# BAAAHS-BRN01-D.net
KiCad netlist of a schematic drawn in EAGLE
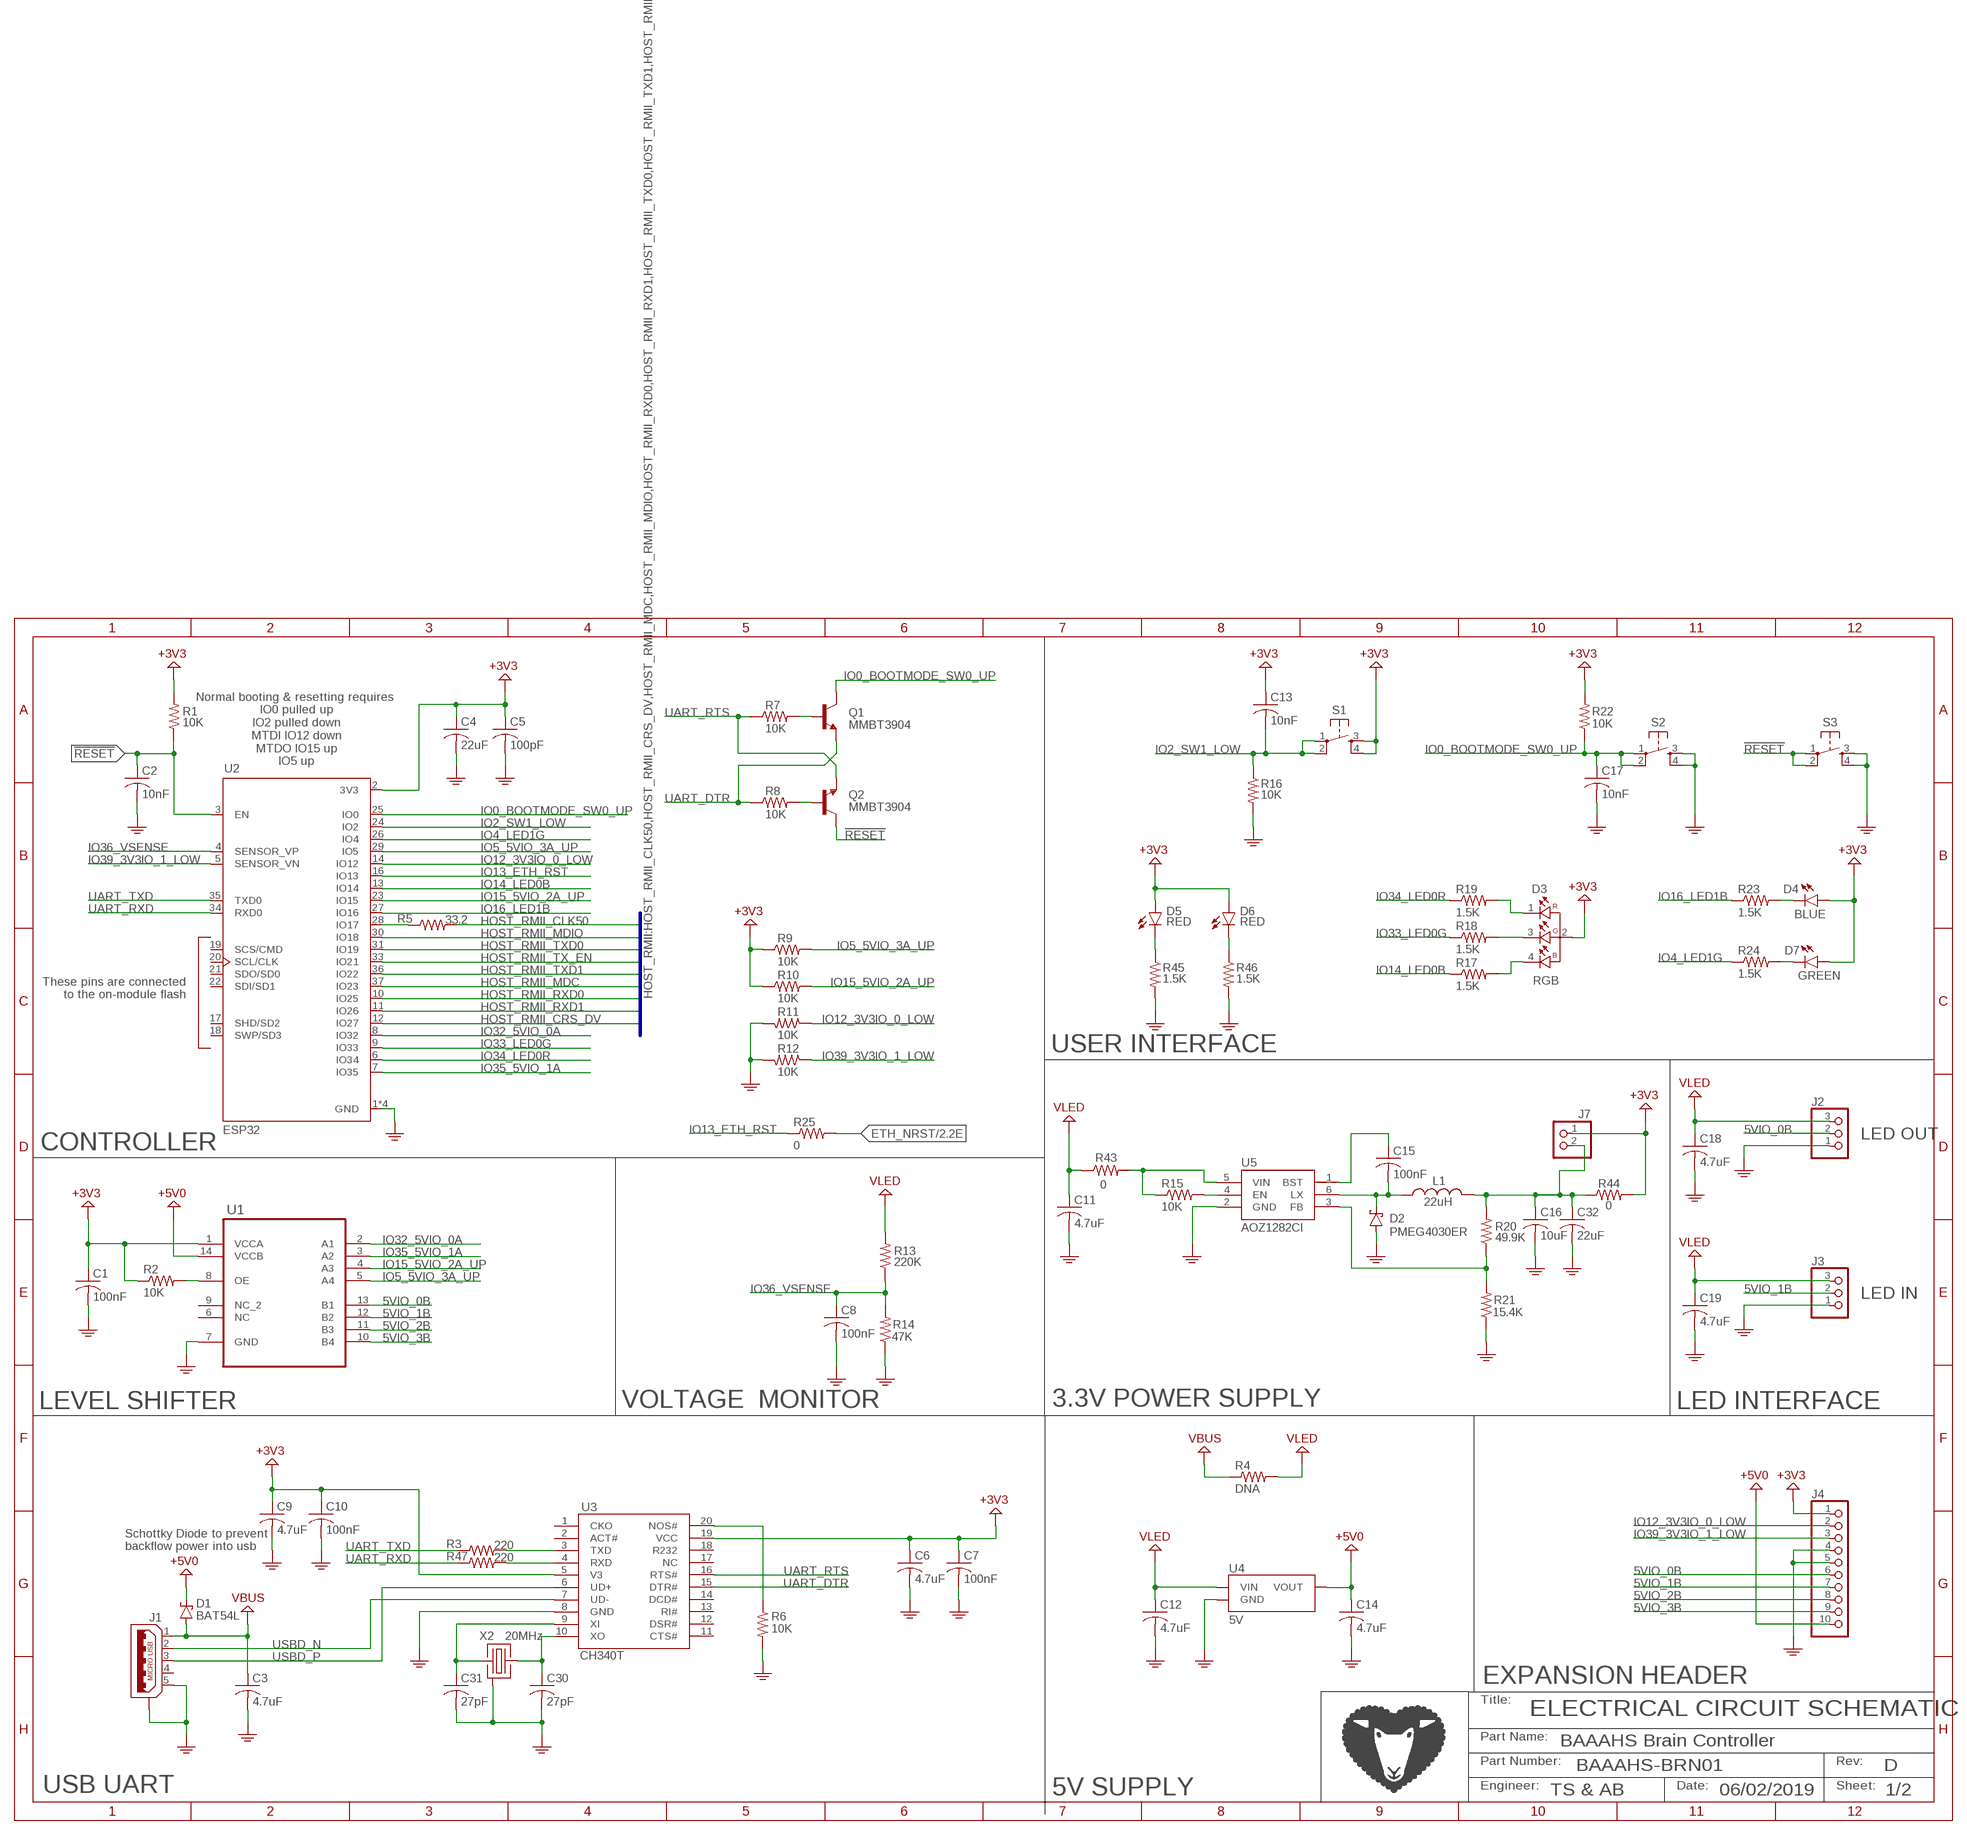
[diagram p0: schematic, sheet 1]
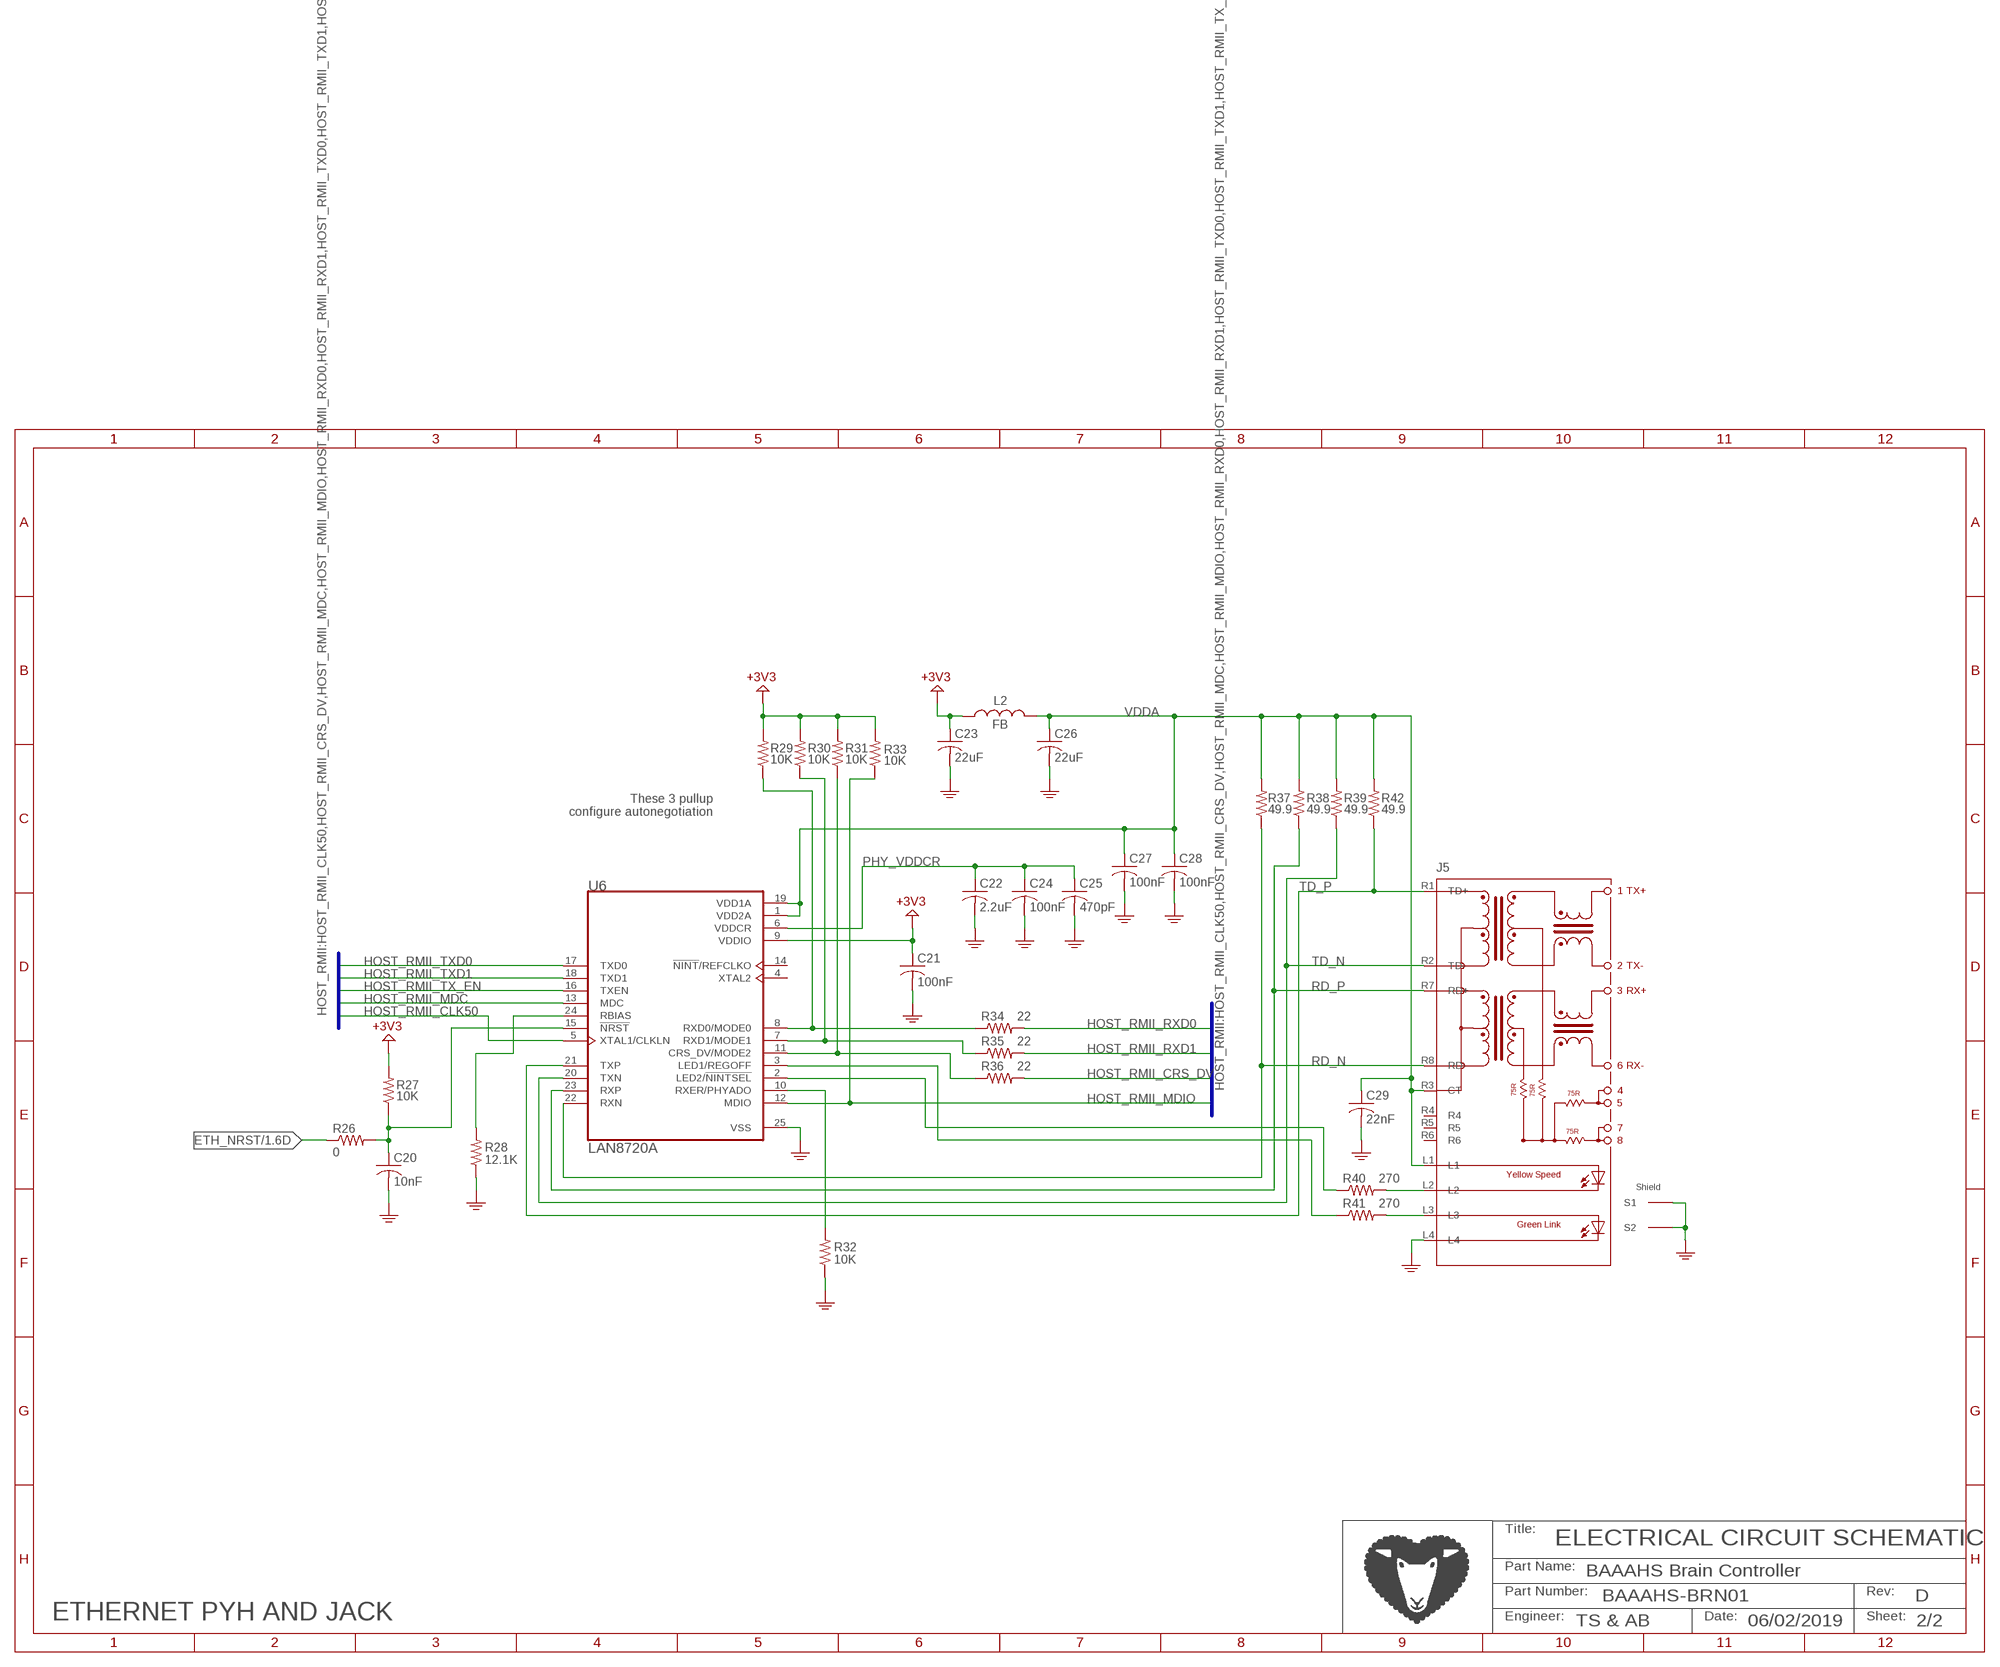
[diagram p1: schematic, sheet 2]

(export (version "E")
  (design (tool "Eeschema 10.0.6"))
  (components
    (comp (ref "C20")
      (value "10nF")
      (footprint "eagle-import:C0402")
      (fields (field (name "TOLERANCE") "+/-10%") (field (name "VOLTAGE") "16V"))
      (libsource (lib "eagle-import") (part "C-C0402-10NF_16V_10%"))
    )
    (comp (ref "C21")
      (value "100nF")
      (footprint "eagle-import:C0402")
      (fields (field (name "TOLERANCE") "+/-10%") (field (name "VOLTAGE") "25V"))
      (libsource (lib "eagle-import") (part "C-C0402-100NF_25V_10%"))
    )
    (comp (ref "C22")
      (value "2.2uF")
      (footprint "eagle-import:C0603")
      (fields (field (name "TOLERANCE") "+/-10%") (field (name "VOLTAGE") "16V"))
      (libsource (lib "eagle-import") (part "C-C0603-2.2UF_16V_10%"))
    )
    (comp (ref "C23")
      (value "22uF")
      (footprint "eagle-import:C0603")
      (fields (field (name "TOLERANCE") "+/-20%") (field (name "VOLTAGE") "10V"))
      (libsource (lib "eagle-import") (part "C-C0603-22UF_10V_20%"))
    )
    (comp (ref "C24")
      (value "100nF")
      (footprint "eagle-import:C0402")
      (fields (field (name "TOLERANCE") "+/-10%") (field (name "VOLTAGE") "25V"))
      (libsource (lib "eagle-import") (part "C-C0402-100NF_25V_10%"))
    )
    (comp (ref "C25")
      (value "470pF")
      (footprint "eagle-import:C0402")
      (fields (field (name "TOLERANCE") "+/-10%") (field (name "VOLTAGE") "50V"))
      (libsource (lib "eagle-import") (part "C-C0402-470PF_50V_10%"))
    )
    (comp (ref "C26")
      (value "22uF")
      (footprint "eagle-import:C0603")
      (fields (field (name "TOLERANCE") "+/-20%") (field (name "VOLTAGE") "10V"))
      (libsource (lib "eagle-import") (part "C-C0603-22UF_10V_20%"))
    )
    (comp (ref "C27")
      (value "100nF")
      (footprint "eagle-import:C0402")
      (fields (field (name "TOLERANCE") "+/-10%") (field (name "VOLTAGE") "25V"))
      (libsource (lib "eagle-import") (part "C-C0402-100NF_25V_10%"))
    )
    (comp (ref "C28")
      (value "100nF")
      (footprint "eagle-import:C0402")
      (fields (field (name "TOLERANCE") "+/-10%") (field (name "VOLTAGE") "25V"))
      (libsource (lib "eagle-import") (part "C-C0402-100NF_25V_10%"))
    )
    (comp (ref "C29")
      (value "22nF")
      (footprint "eagle-import:C0402")
      (fields (field (name "TOLERANCE") "+/-10%") (field (name "VOLTAGE") "16V"))
      (libsource (lib "eagle-import") (part "C-C0402-22NF_16V_10%"))
    )
    (comp (ref "J5")
      (value "RB1-125BAG1A")
      (footprint "eagle-import:WIZNET_RB1-125BAG1A")
      (libsource (lib "eagle-import") (part "RB1-125BAG1A"))
    )
    (comp (ref "L2")
      (value "FB")
      (footprint "eagle-import:L0603")
      (libsource (lib "eagle-import") (part "FB-L0603-0.45OHM_470OHM_200MA"))
    )
    (comp (ref "R26")
      (value "0")
      (footprint "eagle-import:R0402")
      (fields (field (name "POWER") "1/16W") (field (name "TOLERANCE") "1%"))
      (libsource (lib "eagle-import") (part "R-R0402-0_1%"))
    )
    (comp (ref "R27")
      (value "10K")
      (footprint "eagle-import:R0402")
      (fields (field (name "POWER") "1/16W") (field (name "TOLERANCE") "1%"))
      (libsource (lib "eagle-import") (part "R-R0402-10K_1%"))
    )
    (comp (ref "R28")
      (value "12.1K")
      (footprint "eagle-import:R0402")
      (fields (field (name "POWER") "1/16W") (field (name "TOLERANCE") "1%"))
      (libsource (lib "eagle-import") (part "R-R0402-12.1K_1%"))
    )
    (comp (ref "R29")
      (value "10K")
      (footprint "eagle-import:R0402")
      (fields (field (name "POWER") "1/16W") (field (name "TOLERANCE") "1%"))
      (libsource (lib "eagle-import") (part "R-R0402-10K_1%"))
    )
    (comp (ref "R30")
      (value "10K")
      (footprint "eagle-import:R0402")
      (fields (field (name "POWER") "1/16W") (field (name "TOLERANCE") "1%"))
      (libsource (lib "eagle-import") (part "R-R0402-10K_1%"))
    )
    (comp (ref "R31")
      (value "10K")
      (footprint "eagle-import:R0402")
      (fields (field (name "POWER") "1/16W") (field (name "TOLERANCE") "1%"))
      (libsource (lib "eagle-import") (part "R-R0402-10K_1%"))
    )
    (comp (ref "R32")
      (value "10K")
      (footprint "eagle-import:R0402")
      (fields (field (name "POWER") "1/16W") (field (name "TOLERANCE") "1%"))
      (libsource (lib "eagle-import") (part "R-R0402-10K_1%"))
    )
    (comp (ref "R33")
      (value "10K")
      (footprint "eagle-import:R0402")
      (fields (field (name "POWER") "1/16W") (field (name "TOLERANCE") "1%"))
      (libsource (lib "eagle-import") (part "R-R0402-10K_1%"))
    )
    (comp (ref "R34")
      (value "22")
      (footprint "eagle-import:R0402")
      (fields (field (name "POWER") "1/16W") (field (name "TOLERANCE") "1%"))
      (libsource (lib "eagle-import") (part "R-R0402-22_1%"))
    )
    (comp (ref "R35")
      (value "22")
      (footprint "eagle-import:R0402")
      (fields (field (name "POWER") "1/16W") (field (name "TOLERANCE") "1%"))
      (libsource (lib "eagle-import") (part "R-R0402-22_1%"))
    )
    (comp (ref "R36")
      (value "22")
      (footprint "eagle-import:R0402")
      (fields (field (name "POWER") "1/16W") (field (name "TOLERANCE") "1%"))
      (libsource (lib "eagle-import") (part "R-R0402-22_1%"))
    )
    (comp (ref "R37")
      (value "49.9")
      (footprint "eagle-import:R0402")
      (fields (field (name "POWER") "1/16W") (field (name "TOLERANCE") "1%"))
      (libsource (lib "eagle-import") (part "R-R0402-49.9_1%"))
    )
    (comp (ref "R38")
      (value "49.9")
      (footprint "eagle-import:R0402")
      (fields (field (name "POWER") "1/16W") (field (name "TOLERANCE") "1%"))
      (libsource (lib "eagle-import") (part "R-R0402-49.9_1%"))
    )
    (comp (ref "R39")
      (value "49.9")
      (footprint "eagle-import:R0402")
      (fields (field (name "POWER") "1/16W") (field (name "TOLERANCE") "1%"))
      (libsource (lib "eagle-import") (part "R-R0402-49.9_1%"))
    )
    (comp (ref "R40")
      (value "270")
      (footprint "eagle-import:R0402")
      (fields (field (name "POWER") "1/16W") (field (name "TOLERANCE") "1%"))
      (libsource (lib "eagle-import") (part "R-R0402-270_1%"))
    )
    (comp (ref "R41")
      (value "270")
      (footprint "eagle-import:R0402")
      (fields (field (name "POWER") "1/16W") (field (name "TOLERANCE") "1%"))
      (libsource (lib "eagle-import") (part "R-R0402-270_1%"))
    )
    (comp (ref "R42")
      (value "49.9")
      (footprint "eagle-import:R0402")
      (fields (field (name "POWER") "1/16W") (field (name "TOLERANCE") "1%"))
      (libsource (lib "eagle-import") (part "R-R0402-49.9_1%"))
    )
    (comp (ref "U6")
      (value "LAN8720A")
      (footprint "eagle-import:QFN50P400X400X100-25N")
      (libsource (lib "eagle-import") (part "LAN8720A-CP"))
    )
    (comp (ref "C1")
      (value "100nF")
      (footprint "eagle-import:C0402")
      (fields (field (name "TOLERANCE") "+/-10%") (field (name "VOLTAGE") "25V"))
      (libsource (lib "eagle-import") (part "C-C0402-100NF_25V_10%"))
    )
    (comp (ref "C2")
      (value "10nF")
      (footprint "eagle-import:C0402")
      (fields (field (name "TOLERANCE") "+/-10%") (field (name "VOLTAGE") "16V"))
      (libsource (lib "eagle-import") (part "C-C0402-10NF_16V_10%"))
    )
    (comp (ref "C3")
      (value "4.7uF")
      (footprint "eagle-import:C0402")
      (fields (field (name "TOLERANCE") "+/-10%") (field (name "VOLTAGE") "10V"))
      (libsource (lib "eagle-import") (part "C-C0402-4.7UF_10V_10%"))
    )
    (comp (ref "C4")
      (value "22uF")
      (footprint "eagle-import:C0603")
      (fields (field (name "TOLERANCE") "+/-20%") (field (name "VOLTAGE") "10V"))
      (libsource (lib "eagle-import") (part "C-C0603-22UF_10V_20%"))
    )
    (comp (ref "C5")
      (value "100pF")
      (footprint "eagle-import:C0402")
      (fields (field (name "TOLERANCE") "+/-5%") (field (name "VOLTAGE") "50V"))
      (libsource (lib "eagle-import") (part "C-C0402-100PF_50V_5%"))
    )
    (comp (ref "C6")
      (value "4.7uF")
      (footprint "eagle-import:C0402")
      (fields (field (name "TOLERANCE") "+/-10%") (field (name "VOLTAGE") "10V"))
      (libsource (lib "eagle-import") (part "C-C0402-4.7UF_10V_10%"))
    )
    (comp (ref "C7")
      (value "100nF")
      (footprint "eagle-import:C0402")
      (fields (field (name "TOLERANCE") "+/-10%") (field (name "VOLTAGE") "25V"))
      (libsource (lib "eagle-import") (part "C-C0402-100NF_25V_10%"))
    )
    (comp (ref "C8")
      (value "100nF")
      (footprint "eagle-import:C0402")
      (fields (field (name "TOLERANCE") "+/-10%") (field (name "VOLTAGE") "25V"))
      (libsource (lib "eagle-import") (part "C-C0402-100NF_25V_10%"))
    )
    (comp (ref "C9")
      (value "4.7uF")
      (footprint "eagle-import:C0402")
      (fields (field (name "TOLERANCE") "+/-10%") (field (name "VOLTAGE") "10V"))
      (libsource (lib "eagle-import") (part "C-C0402-4.7UF_10V_10%"))
    )
    (comp (ref "C10")
      (value "100nF")
      (footprint "eagle-import:C0402")
      (fields (field (name "TOLERANCE") "+/-10%") (field (name "VOLTAGE") "25V"))
      (libsource (lib "eagle-import") (part "C-C0402-100NF_25V_10%"))
    )
    (comp (ref "C11")
      (value "4.7uF")
      (footprint "eagle-import:C0603")
      (fields (field (name "TOLERANCE") "+/-10%") (field (name "VOLTAGE") "25V"))
      (libsource (lib "eagle-import") (part "C-C0603-4.7UF_25V_10%"))
    )
    (comp (ref "C12")
      (value "4.7uF")
      (footprint "eagle-import:C0603")
      (fields (field (name "TOLERANCE") "+/-10%") (field (name "VOLTAGE") "25V"))
      (libsource (lib "eagle-import") (part "C-C0603-4.7UF_25V_10%"))
    )
    (comp (ref "C13")
      (value "10nF")
      (footprint "eagle-import:C0402")
      (fields (field (name "TOLERANCE") "+/-10%") (field (name "VOLTAGE") "16V"))
      (libsource (lib "eagle-import") (part "C-C0402-10NF_16V_10%"))
    )
    (comp (ref "C14")
      (value "4.7uF")
      (footprint "eagle-import:C0402")
      (fields (field (name "TOLERANCE") "+/-10%") (field (name "VOLTAGE") "10V"))
      (libsource (lib "eagle-import") (part "C-C0402-4.7UF_10V_10%"))
    )
    (comp (ref "C15")
      (value "100nF")
      (footprint "eagle-import:C0402")
      (fields (field (name "TOLERANCE") "+/-10%") (field (name "VOLTAGE") "25V"))
      (libsource (lib "eagle-import") (part "C-C0402-100NF_25V_10%"))
    )
    (comp (ref "C16")
      (value "10uF")
      (footprint "eagle-import:C0603")
      (fields (field (name "TOLERANCE") "+/-20%") (field (name "VOLTAGE") "25V"))
      (libsource (lib "eagle-import") (part "C-C0603-10UF_25V_20%"))
    )
    (comp (ref "C17")
      (value "10nF")
      (footprint "eagle-import:C0402")
      (fields (field (name "TOLERANCE") "+/-10%") (field (name "VOLTAGE") "16V"))
      (libsource (lib "eagle-import") (part "C-C0402-10NF_16V_10%"))
    )
    (comp (ref "C18")
      (value "4.7uF")
      (footprint "eagle-import:C0603")
      (fields (field (name "TOLERANCE") "+/-10%") (field (name "VOLTAGE") "25V"))
      (libsource (lib "eagle-import") (part "C-C0603-4.7UF_25V_10%"))
    )
    (comp (ref "C19")
      (value "4.7uF")
      (footprint "eagle-import:C0603")
      (fields (field (name "TOLERANCE") "+/-10%") (field (name "VOLTAGE") "25V"))
      (libsource (lib "eagle-import") (part "C-C0603-4.7UF_25V_10%"))
    )
    (comp (ref "C30")
      (value "27pF")
      (footprint "eagle-import:C0402")
      (fields (field (name "TOLERANCE") "+/-5%") (field (name "VOLTAGE") "50V"))
      (libsource (lib "eagle-import") (part "C-C0402-27PF_50V_5%"))
    )
    (comp (ref "C31")
      (value "27pF")
      (footprint "eagle-import:C0402")
      (fields (field (name "TOLERANCE") "+/-5%") (field (name "VOLTAGE") "50V"))
      (libsource (lib "eagle-import") (part "C-C0402-27PF_50V_5%"))
    )
    (comp (ref "C32")
      (value "22uF")
      (footprint "eagle-import:C0603")
      (fields (field (name "TOLERANCE") "+/-20%") (field (name "VOLTAGE") "10V"))
      (libsource (lib "eagle-import") (part "C-C0603-22UF_10V_20%"))
    )
    (comp (ref "D1")
      (value "BAT54L")
      (footprint "eagle-import:SOT23")
      (libsource (lib "eagle-import") (part "D_SCHOTTKY-SOT23"))
    )
    (comp (ref "D2")
      (value "PMEG4030ER")
      (footprint "eagle-import:SOD123")
      (libsource (lib "eagle-import") (part "D_SCHOTTKY-SOD123-PMEG4030ER_40V"))
    )
    (comp (ref "D3")
      (value "RGB")
      (footprint "eagle-import:RGB1616")
      (libsource (lib "eagle-import") (part "RGB_LED-RGB1616"))
    )
    (comp (ref "D4")
      (value "BLUE")
      (footprint "eagle-import:D0603")
      (libsource (lib "eagle-import") (part "LED-D0603-BLUE_29MCD"))
    )
    (comp (ref "D5")
      (value "RED")
      (footprint "eagle-import:D0603")
      (libsource (lib "eagle-import") (part "LED-D0603-RED_54MCD"))
    )
    (comp (ref "D6")
      (value "RED")
      (footprint "eagle-import:D0603")
      (libsource (lib "eagle-import") (part "LED-D0603-RED_54MCD"))
    )
    (comp (ref "D7")
      (value "GREEN")
      (footprint "eagle-import:D0603")
      (libsource (lib "eagle-import") (part "LED-D0603-GREEN_35MCD"))
    )
    (comp (ref "J1")
      (value "USB_MICRO-FCI-USB_MICRO_A_RA")
      (footprint "eagle-import:USB_MICRO_A_RA")
      (libsource (lib "eagle-import") (part "USB_MICRO-USB_MICRO_A_RA-FCI"))
    )
    (comp (ref "J2")
      (value "PINHD1X3-20AWG")
      (footprint "eagle-import:3WAY_LED_WIRES")
      (libsource (lib "eagle-import") (part "PINHD1X3-20AWG"))
    )
    (comp (ref "J3")
      (value "PINHD1X3-20AWG")
      (footprint "eagle-import:3WAY_LED_WIRES")
      (libsource (lib "eagle-import") (part "PINHD1X3-20AWG"))
    )
    (comp (ref "J4")
      (value "PINHD1X10-1X10")
      (footprint "eagle-import:1X10")
      (libsource (lib "eagle-import") (part "PINHD1X10-1X10"))
    )
    (comp (ref "J7")
      (value "PINHD1X2-1X02")
      (footprint "eagle-import:1X02")
      (libsource (lib "eagle-import") (part "PINHD1X2-1X02"))
    )
    (comp (ref "L1")
      (value "22uH")
      (footprint "eagle-import:NRG4026")
      (libsource (lib "eagle-import") (part "L-NRG4026-22UH__290MOHM_700MA"))
    )
    (comp (ref "Q1")
      (value "MMBT3904")
      (footprint "eagle-import:SOT23")
      (fields (field (name "VOLTAGE") "40V"))
      (libsource (lib "eagle-import") (part "NPN-SOT23-MMBT3904_40V"))
    )
    (comp (ref "Q2")
      (value "MMBT3904")
      (footprint "eagle-import:SOT23")
      (fields (field (name "VOLTAGE") "40V"))
      (libsource (lib "eagle-import") (part "NPN-SOT23-MMBT3904_40V"))
    )
    (comp (ref "R1")
      (value "10K")
      (footprint "eagle-import:R0402")
      (fields (field (name "POWER") "1/16W") (field (name "TOLERANCE") "1%"))
      (libsource (lib "eagle-import") (part "R-R0402-10K_1%"))
    )
    (comp (ref "R2")
      (value "10K")
      (footprint "eagle-import:R0402")
      (fields (field (name "POWER") "1/16W") (field (name "TOLERANCE") "1%"))
      (libsource (lib "eagle-import") (part "R-R0402-10K_1%"))
    )
    (comp (ref "R3")
      (value "220")
      (footprint "eagle-import:R0402")
      (fields (field (name "POWER") "1/16W") (field (name "TOLERANCE") "1%"))
      (libsource (lib "eagle-import") (part "R-R0402-220_1%"))
    )
    (comp (ref "R4")
      (value "DNA")
      (footprint "eagle-import:R0603")
      (fields (field (name "POWER") "1/16W"))
      (libsource (lib "eagle-import") (part "R-R0603-DNA"))
    )
    (comp (ref "R5")
      (value "33.2")
      (footprint "eagle-import:R0402")
      (fields (field (name "POWER") "1/16W") (field (name "TOLERANCE") "1%"))
      (libsource (lib "eagle-import") (part "R-R0402-33.2_1%"))
    )
    (comp (ref "R6")
      (value "10K")
      (footprint "eagle-import:R0402")
      (fields (field (name "POWER") "1/16W") (field (name "TOLERANCE") "1%"))
      (libsource (lib "eagle-import") (part "R-R0402-10K_1%"))
    )
    (comp (ref "R7")
      (value "10K")
      (footprint "eagle-import:R0402")
      (fields (field (name "POWER") "1/16W") (field (name "TOLERANCE") "1%"))
      (libsource (lib "eagle-import") (part "R-R0402-10K_1%"))
    )
    (comp (ref "R8")
      (value "10K")
      (footprint "eagle-import:R0402")
      (fields (field (name "POWER") "1/16W") (field (name "TOLERANCE") "1%"))
      (libsource (lib "eagle-import") (part "R-R0402-10K_1%"))
    )
    (comp (ref "R9")
      (value "10K")
      (footprint "eagle-import:R0402")
      (fields (field (name "POWER") "1/16W") (field (name "TOLERANCE") "1%"))
      (libsource (lib "eagle-import") (part "R-R0402-10K_1%"))
    )
    (comp (ref "R10")
      (value "10K")
      (footprint "eagle-import:R0402")
      (fields (field (name "POWER") "1/16W") (field (name "TOLERANCE") "1%"))
      (libsource (lib "eagle-import") (part "R-R0402-10K_1%"))
    )
    (comp (ref "R11")
      (value "10K")
      (footprint "eagle-import:R0402")
      (fields (field (name "POWER") "1/16W") (field (name "TOLERANCE") "1%"))
      (libsource (lib "eagle-import") (part "R-R0402-10K_1%"))
    )
    (comp (ref "R12")
      (value "10K")
      (footprint "eagle-import:R0402")
      (fields (field (name "POWER") "1/16W") (field (name "TOLERANCE") "1%"))
      (libsource (lib "eagle-import") (part "R-R0402-10K_1%"))
    )
    (comp (ref "R13")
      (value "220K")
      (footprint "eagle-import:R0402")
      (fields (field (name "POWER") "1/16W") (field (name "TOLERANCE") "1%"))
      (libsource (lib "eagle-import") (part "R-R0402-220K_1%"))
    )
    (comp (ref "R14")
      (value "47K")
      (footprint "eagle-import:R0402")
      (fields (field (name "POWER") "1/16W") (field (name "TOLERANCE") "1%"))
      (libsource (lib "eagle-import") (part "R-R0402-47K_1%"))
    )
    (comp (ref "R15")
      (value "10K")
      (footprint "eagle-import:R0402")
      (fields (field (name "POWER") "1/16W") (field (name "TOLERANCE") "1%"))
      (libsource (lib "eagle-import") (part "R-R0402-10K_1%"))
    )
    (comp (ref "R16")
      (value "10K")
      (footprint "eagle-import:R0402")
      (fields (field (name "POWER") "1/16W") (field (name "TOLERANCE") "1%"))
      (libsource (lib "eagle-import") (part "R-R0402-10K_1%"))
    )
    (comp (ref "R17")
      (value "1.5K")
      (footprint "eagle-import:R0402")
      (fields (field (name "POWER") "1/16W") (field (name "TOLERANCE") "1%"))
      (libsource (lib "eagle-import") (part "R-R0402-1.5K_1%"))
    )
    (comp (ref "R18")
      (value "1.5K")
      (footprint "eagle-import:R0402")
      (fields (field (name "POWER") "1/16W") (field (name "TOLERANCE") "1%"))
      (libsource (lib "eagle-import") (part "R-R0402-1.5K_1%"))
    )
    (comp (ref "R19")
      (value "1.5K")
      (footprint "eagle-import:R0402")
      (fields (field (name "POWER") "1/16W") (field (name "TOLERANCE") "1%"))
      (libsource (lib "eagle-import") (part "R-R0402-1.5K_1%"))
    )
    (comp (ref "R20")
      (value "49.9K")
      (footprint "eagle-import:R0402")
      (fields (field (name "POWER") "1/16W") (field (name "TOLERANCE") "1%"))
      (libsource (lib "eagle-import") (part "R-R0402-49.9K_1%"))
    )
    (comp (ref "R21")
      (value "15.4K")
      (footprint "eagle-import:R0402")
      (fields (field (name "POWER") "1/16W") (field (name "TOLERANCE") "1%"))
      (libsource (lib "eagle-import") (part "R-R0402-15.4K_1%"))
    )
    (comp (ref "R22")
      (value "10K")
      (footprint "eagle-import:R0402")
      (fields (field (name "POWER") "1/16W") (field (name "TOLERANCE") "1%"))
      (libsource (lib "eagle-import") (part "R-R0402-10K_1%"))
    )
    (comp (ref "R23")
      (value "1.5K")
      (footprint "eagle-import:R0402")
      (fields (field (name "POWER") "1/16W") (field (name "TOLERANCE") "1%"))
      (libsource (lib "eagle-import") (part "R-R0402-1.5K_1%"))
    )
    (comp (ref "R24")
      (value "1.5K")
      (footprint "eagle-import:R0402")
      (fields (field (name "POWER") "1/16W") (field (name "TOLERANCE") "1%"))
      (libsource (lib "eagle-import") (part "R-R0402-1.5K_1%"))
    )
    (comp (ref "R25")
      (value "0")
      (footprint "eagle-import:R0402")
      (fields (field (name "POWER") "1/16W") (field (name "TOLERANCE") "1%"))
      (libsource (lib "eagle-import") (part "R-R0402-0_1%"))
    )
    (comp (ref "R43")
      (value "0")
      (footprint "eagle-import:R0603")
      (fields (field (name "POWER") "1/10W") (field (name "TOLERANCE") "1%"))
      (libsource (lib "eagle-import") (part "R-R0603-0_1%"))
    )
    (comp (ref "R44")
      (value "0")
      (footprint "eagle-import:R0603")
      (fields (field (name "POWER") "1/10W") (field (name "TOLERANCE") "1%"))
      (libsource (lib "eagle-import") (part "R-R0603-0_1%"))
    )
    (comp (ref "R45")
      (value "1.5K")
      (footprint "eagle-import:R0402")
      (fields (field (name "POWER") "1/16W") (field (name "TOLERANCE") "1%"))
      (libsource (lib "eagle-import") (part "R-R0402-1.5K_1%"))
    )
    (comp (ref "R46")
      (value "1.5K")
      (footprint "eagle-import:R0402")
      (fields (field (name "POWER") "1/16W") (field (name "TOLERANCE") "1%"))
      (libsource (lib "eagle-import") (part "R-R0402-1.5K_1%"))
    )
    (comp (ref "R47")
      (value "220")
      (footprint "eagle-import:R0402")
      (fields (field (name "POWER") "1/16W") (field (name "TOLERANCE") "1%"))
      (libsource (lib "eagle-import") (part "R-R0402-220_1%"))
    )
    (comp (ref "S1")
      (value "SW4-SM6MM")
      (footprint "eagle-import:SM6MM")
      (libsource (lib "eagle-import") (part "SW4-SM6MM"))
    )
    (comp (ref "S2")
      (value "SW4-SM6MM")
      (footprint "eagle-import:SM6MM")
      (libsource (lib "eagle-import") (part "SW4-SM6MM"))
    )
    (comp (ref "S3")
      (value "SW4-SM6MM")
      (footprint "eagle-import:SM6MM")
      (libsource (lib "eagle-import") (part "SW4-SM6MM"))
    )
    (comp (ref "U1")
      (value "TXB0104PWR")
      (footprint "eagle-import:SOP65P640X120-14N")
      (libsource (lib "eagle-import") (part "TXB0104PWR"))
    )
    (comp (ref "U2")
      (value "ESP32")
      (footprint "eagle-import:MODULE_ESP32WROOM32D")
      (libsource (lib "eagle-import") (part "ESP32WROOM32D-MODULE_ESP32WROOM32D"))
    )
    (comp (ref "U3")
      (value "CH340T")
      (footprint "eagle-import:SSOP20")
      (libsource (lib "eagle-import") (part "CH340T-SSOP20"))
    )
    (comp (ref "U4")
      (value "5V")
      (footprint "eagle-import:SOT23")
      (libsource (lib "eagle-import") (part "SE8550X2-SOT23"))
    )
    (comp (ref "U5")
      (value "AOZ1282CI")
      (footprint "eagle-import:SOT23_6")
      (libsource (lib "eagle-import") (part "AOZ1282CI-SOT23_6"))
    )
    (comp (ref "X2")
      (value "20MHz")
      (footprint "eagle-import:3.2X2.5_4P")
      (libsource (lib "eagle-import") (part "XTAL33.2X2.5_4P-20MHZ_20PF_30PPM"))
    )
  )
  (nets
    (net (code "5") (name "3V3") (class "Default")
      (node (ref "C1") (pin "1") (pinfunction "1_1") (pintype "passive"))
      (node (ref "C10") (pin "1") (pinfunction "1_1") (pintype "passive"))
      (node (ref "C13") (pin "1") (pinfunction "1_1") (pintype "passive"))
      (node (ref "C21") (pin "1") (pinfunction "1_1") (pintype "passive"))
      (node (ref "C23") (pin "1") (pinfunction "1_1") (pintype "passive"))
      (node (ref "C4") (pin "1") (pinfunction "1_1") (pintype "passive"))
      (node (ref "C5") (pin "1") (pinfunction "1_1") (pintype "passive"))
      (node (ref "C6") (pin "1") (pinfunction "1_1") (pintype "passive"))
      (node (ref "C7") (pin "1") (pinfunction "1_1") (pintype "passive"))
      (node (ref "C9") (pin "1") (pinfunction "1_1") (pintype "passive"))
      (node (ref "D3") (pin "2") (pinfunction "CA_2") (pintype "passive"))
      (node (ref "D4") (pin "A") (pinfunction "A_A") (pintype "passive"))
      (node (ref "D5") (pin "A") (pinfunction "A_A") (pintype "passive"))
      (node (ref "D6") (pin "A") (pinfunction "A_A") (pintype "passive"))
      (node (ref "D7") (pin "A") (pinfunction "A_A") (pintype "passive"))
      (node (ref "J4") (pin "1") (pinfunction "1_1") (pintype "passive"))
      (node (ref "J7") (pin "1") (pinfunction "1_1") (pintype "passive"))
      (node (ref "L2") (pin "1") (pinfunction "1_1") (pintype "passive"))
      (node (ref "R1") (pin "2") (pinfunction "2_2") (pintype "passive"))
      (node (ref "R10") (pin "1") (pinfunction "1_1") (pintype "passive"))
      (node (ref "R2") (pin "1") (pinfunction "1_1") (pintype "passive"))
      (node (ref "R22") (pin "2") (pinfunction "2_2") (pintype "passive"))
      (node (ref "R27") (pin "2") (pinfunction "2_2") (pintype "passive"))
      (node (ref "R29") (pin "2") (pinfunction "2_2") (pintype "passive"))
      (node (ref "R30") (pin "2") (pinfunction "2_2") (pintype "passive"))
      (node (ref "R31") (pin "2") (pinfunction "2_2") (pintype "passive"))
      (node (ref "R33") (pin "2") (pinfunction "2_2") (pintype "passive"))
      (node (ref "R44") (pin "2") (pinfunction "2_2") (pintype "passive"))
      (node (ref "R9") (pin "1") (pinfunction "1_1") (pintype "passive"))
      (node (ref "S1") (pin "3") (pinfunction "S_3") (pintype "passive"))
      (node (ref "S1") (pin "4") (pinfunction "S1_4") (pintype "passive"))
      (node (ref "U1") (pin "1") (pinfunction "VCCA_1") (pintype "power_in"))
      (node (ref "U2") (pin "2") (pinfunction "3V3_2") (pintype "power_in"))
      (node (ref "U3") (pin "19") (pinfunction "VCC_19") (pintype "power_in"))
      (node (ref "U3") (pin "5") (pinfunction "V3_5") (pintype "power_in"))
      (node (ref "U6") (pin "9") (pinfunction "VDDIO_9") (pintype "power_in"))
    )
    (net (code "6") (name "5V0") (class "Default")
      (node (ref "C14") (pin "1") (pinfunction "1_1") (pintype "passive"))
      (node (ref "D1") (pin "3") (pinfunction "C_3") (pintype "passive"))
      (node (ref "J4") (pin "10") (pinfunction "10_10") (pintype "passive"))
      (node (ref "U1") (pin "14") (pinfunction "VCCB_14") (pintype "power_in"))
      (node (ref "U4") (pin "2") (pinfunction "VOUT_2") (pintype "bidirectional"))
    )
    (net (code "7") (name "5VIO_0B") (class "Default")
      (node (ref "J2") (pin "2") (pinfunction "2_2") (pintype "passive"))
      (node (ref "J4") (pin "6") (pinfunction "6_6") (pintype "passive"))
      (node (ref "U1") (pin "13") (pinfunction "B1_13") (pintype "bidirectional"))
    )
    (net (code "8") (name "5VIO_1B") (class "Default")
      (node (ref "J3") (pin "2") (pinfunction "2_2") (pintype "passive"))
      (node (ref "J4") (pin "7") (pinfunction "7_7") (pintype "passive"))
      (node (ref "U1") (pin "12") (pinfunction "B2_12") (pintype "bidirectional"))
    )
    (net (code "9") (name "5VIO_2B") (class "Default")
      (node (ref "J4") (pin "8") (pinfunction "8_8") (pintype "passive"))
      (node (ref "U1") (pin "11") (pinfunction "B3_11") (pintype "bidirectional"))
    )
    (net (code "10") (name "5VIO_3B") (class "Default")
      (node (ref "J4") (pin "9") (pinfunction "9_9") (pintype "passive"))
      (node (ref "U1") (pin "10") (pinfunction "B4_10") (pintype "bidirectional"))
    )
    (net (code "11") (name "ETH_NRST") (class "Default")
      (node (ref "R25") (pin "2") (pinfunction "2_2") (pintype "passive"))
      (node (ref "R26") (pin "1") (pinfunction "1_1") (pintype "passive"))
    )
    (net (code "12") (name "GND") (class "Default")
      (node (ref "C1") (pin "2") (pinfunction "2_2") (pintype "passive"))
      (node (ref "C10") (pin "2") (pinfunction "2_2") (pintype "passive"))
      (node (ref "C11") (pin "2") (pinfunction "2_2") (pintype "passive"))
      (node (ref "C12") (pin "2") (pinfunction "2_2") (pintype "passive"))
      (node (ref "C14") (pin "2") (pinfunction "2_2") (pintype "passive"))
      (node (ref "C16") (pin "2") (pinfunction "2_2") (pintype "passive"))
      (node (ref "C17") (pin "2") (pinfunction "2_2") (pintype "passive"))
      (node (ref "C18") (pin "2") (pinfunction "2_2") (pintype "passive"))
      (node (ref "C19") (pin "2") (pinfunction "2_2") (pintype "passive"))
      (node (ref "C2") (pin "2") (pinfunction "2_2") (pintype "passive"))
      (node (ref "C20") (pin "2") (pinfunction "2_2") (pintype "passive"))
      (node (ref "C21") (pin "2") (pinfunction "2_2") (pintype "passive"))
      (node (ref "C22") (pin "2") (pinfunction "2_2") (pintype "passive"))
      (node (ref "C23") (pin "2") (pinfunction "2_2") (pintype "passive"))
      (node (ref "C24") (pin "2") (pinfunction "2_2") (pintype "passive"))
      (node (ref "C25") (pin "2") (pinfunction "2_2") (pintype "passive"))
      (node (ref "C26") (pin "2") (pinfunction "2_2") (pintype "passive"))
      (node (ref "C27") (pin "2") (pinfunction "2_2") (pintype "passive"))
      (node (ref "C28") (pin "2") (pinfunction "2_2") (pintype "passive"))
      (node (ref "C29") (pin "2") (pinfunction "2_2") (pintype "passive"))
      (node (ref "C3") (pin "2") (pinfunction "2_2") (pintype "passive"))
      (node (ref "C30") (pin "2") (pinfunction "2_2") (pintype "passive"))
      (node (ref "C31") (pin "2") (pinfunction "2_2") (pintype "passive"))
      (node (ref "C32") (pin "2") (pinfunction "2_2") (pintype "passive"))
      (node (ref "C4") (pin "2") (pinfunction "2_2") (pintype "passive"))
      (node (ref "C5") (pin "2") (pinfunction "2_2") (pintype "passive"))
      (node (ref "C6") (pin "2") (pinfunction "2_2") (pintype "passive"))
      (node (ref "C7") (pin "2") (pinfunction "2_2") (pintype "passive"))
      (node (ref "C8") (pin "2") (pinfunction "2_2") (pintype "passive"))
      (node (ref "C9") (pin "2") (pinfunction "2_2") (pintype "passive"))
      (node (ref "D2") (pin "A") (pinfunction "A_A") (pintype "passive"))
      (node (ref "J1") (pin "5") (pinfunction "5_5") (pintype "passive"))
      (node (ref "J1") (pin "S1") (pinfunction "S1_S1") (pintype "bidirectional"))
      (node (ref "J1") (pin "S2") (pinfunction "S1_S2") (pintype "bidirectional"))
      (node (ref "J1") (pin "S3") (pinfunction "S1_S3") (pintype "bidirectional"))
      (node (ref "J1") (pin "S4") (pinfunction "S1_S4") (pintype "bidirectional"))
      (node (ref "J1") (pin "S5") (pinfunction "S1_S5") (pintype "bidirectional"))
      (node (ref "J1") (pin "S6") (pinfunction "S1_S6") (pintype "bidirectional"))
      (node (ref "J2") (pin "1") (pinfunction "3_1") (pintype "passive"))
      (node (ref "J3") (pin "1") (pinfunction "3_1") (pintype "passive"))
      (node (ref "J4") (pin "4") (pinfunction "4_4") (pintype "passive"))
      (node (ref "J4") (pin "5") (pinfunction "5_5") (pintype "passive"))
      (node (ref "J5") (pin "L4") (pinfunction "L4_L4") (pintype "passive"))
      (node (ref "J5") (pin "S1") (pinfunction "S1_S1") (pintype "power_in"))
      (node (ref "J5") (pin "S2") (pinfunction "S2_S2") (pintype "power_in"))
      (node (ref "R11") (pin "2") (pinfunction "2_2") (pintype "passive"))
      (node (ref "R12") (pin "2") (pinfunction "2_2") (pintype "passive"))
      (node (ref "R14") (pin "1") (pinfunction "1_1") (pintype "passive"))
      (node (ref "R16") (pin "2") (pinfunction "2_2") (pintype "passive"))
      (node (ref "R21") (pin "1") (pinfunction "1_1") (pintype "passive"))
      (node (ref "R28") (pin "1") (pinfunction "1_1") (pintype "passive"))
      (node (ref "R32") (pin "1") (pinfunction "1_1") (pintype "passive"))
      (node (ref "R45") (pin "2") (pinfunction "2_2") (pintype "passive"))
      (node (ref "R46") (pin "2") (pinfunction "2_2") (pintype "passive"))
      (node (ref "R6") (pin "2") (pinfunction "2_2") (pintype "passive"))
      (node (ref "S2") (pin "3") (pinfunction "S_3") (pintype "passive"))
      (node (ref "S2") (pin "4") (pinfunction "S1_4") (pintype "passive"))
      (node (ref "S3") (pin "3") (pinfunction "S_3") (pintype "passive"))
      (node (ref "S3") (pin "4") (pinfunction "S1_4") (pintype "passive"))
      (node (ref "U1") (pin "7") (pinfunction "GND_7") (pintype "passive"))
      (node (ref "U2") (pin "1") (pinfunction "GND_1") (pintype "power_in"))
      (node (ref "U2") (pin "15") (pinfunction "GND_15") (pintype "power_in"))
      (node (ref "U2") (pin "38") (pinfunction "GND_38") (pintype "power_in"))
      (node (ref "U2") (pin "39") (pinfunction "GND_39") (pintype "power_in"))
      (node (ref "U3") (pin "8") (pinfunction "GND_8") (pintype "power_in"))
      (node (ref "U4") (pin "1") (pinfunction "GND_1") (pintype "bidirectional"))
      (node (ref "U5") (pin "2") (pinfunction "GND_2") (pintype "bidirectional"))
      (node (ref "U6") (pin "25") (pinfunction "VSS_25") (pintype "power_in"))
      (node (ref "X2") (pin "2") (pinfunction "SH_2") (pintype "bidirectional"))
      (node (ref "X2") (pin "4") (pinfunction "SH_4") (pintype "bidirectional"))
    )
    (net (code "13") (name "HOST_RMII_CLK50") (class "Default")
      (node (ref "R5") (pin "2") (pinfunction "2_2") (pintype "passive"))
      (node (ref "U6") (pin "5") (pinfunction "XTAL1/CLKLN_5") (pintype "input"))
    )
    (net (code "14") (name "HOST_RMII_CRS_DV") (class "Default")
      (node (ref "R36") (pin "2") (pinfunction "2_2") (pintype "passive"))
      (node (ref "U2") (pin "12") (pinfunction "IO27_12") (pintype "bidirectional"))
    )
    (net (code "15") (name "HOST_RMII_MDC") (class "Default")
      (node (ref "U2") (pin "37") (pinfunction "IO23_37") (pintype "bidirectional"))
      (node (ref "U6") (pin "13") (pinfunction "MDC_13") (pintype "input"))
    )
    (net (code "16") (name "HOST_RMII_MDIO") (class "Default")
      (node (ref "R33") (pin "1") (pinfunction "1_1") (pintype "passive"))
      (node (ref "U2") (pin "30") (pinfunction "IO18_30") (pintype "bidirectional"))
      (node (ref "U6") (pin "12") (pinfunction "MDIO_12") (pintype "bidirectional"))
    )
    (net (code "17") (name "HOST_RMII_RXD0") (class "Default")
      (node (ref "R34") (pin "2") (pinfunction "2_2") (pintype "passive"))
      (node (ref "U2") (pin "10") (pinfunction "IO25_10") (pintype "bidirectional"))
    )
    (net (code "18") (name "HOST_RMII_RXD1") (class "Default")
      (node (ref "R35") (pin "2") (pinfunction "2_2") (pintype "passive"))
      (node (ref "U2") (pin "11") (pinfunction "IO26_11") (pintype "bidirectional"))
    )
    (net (code "19") (name "HOST_RMII_TXD0") (class "Default")
      (node (ref "U2") (pin "31") (pinfunction "IO19_31") (pintype "bidirectional"))
      (node (ref "U6") (pin "17") (pinfunction "TXD0_17") (pintype "input"))
    )
    (net (code "20") (name "HOST_RMII_TXD1") (class "Default")
      (node (ref "U2") (pin "36") (pinfunction "IO22_36") (pintype "bidirectional"))
      (node (ref "U6") (pin "18") (pinfunction "TXD1_18") (pintype "input"))
    )
    (net (code "21") (name "HOST_RMII_TX_EN") (class "Default")
      (node (ref "U2") (pin "33") (pinfunction "IO21_33") (pintype "bidirectional"))
      (node (ref "U6") (pin "16") (pinfunction "TXEN_16") (pintype "input"))
    )
    (net (code "22") (name "IO0_BOOTMODE_SW0_UP") (class "Default")
      (node (ref "C17") (pin "1") (pinfunction "1_1") (pintype "passive"))
      (node (ref "Q1") (pin "3") (pinfunction "C_3") (pintype "passive"))
      (node (ref "R22") (pin "1") (pinfunction "1_1") (pintype "passive"))
      (node (ref "S2") (pin "1") (pinfunction "P_1") (pintype "passive"))
      (node (ref "S2") (pin "2") (pinfunction "P1_2") (pintype "passive"))
      (node (ref "U2") (pin "25") (pinfunction "IO0_25") (pintype "bidirectional"))
    )
    (net (code "23") (name "IO2_SW1_LOW") (class "Default")
      (node (ref "C13") (pin "2") (pinfunction "2_2") (pintype "passive"))
      (node (ref "R16") (pin "1") (pinfunction "1_1") (pintype "passive"))
      (node (ref "S1") (pin "1") (pinfunction "P_1") (pintype "passive"))
      (node (ref "S1") (pin "2") (pinfunction "P1_2") (pintype "passive"))
      (node (ref "U2") (pin "24") (pinfunction "IO2_24") (pintype "bidirectional"))
    )
    (net (code "24") (name "IO4_LED1G") (class "Default")
      (node (ref "R24") (pin "1") (pinfunction "1_1") (pintype "passive"))
      (node (ref "U2") (pin "26") (pinfunction "IO4_26") (pintype "bidirectional"))
    )
    (net (code "25") (name "IO5_5VIO_3A_UP") (class "Default")
      (node (ref "R9") (pin "2") (pinfunction "2_2") (pintype "passive"))
      (node (ref "U1") (pin "5") (pinfunction "A4_5") (pintype "bidirectional"))
      (node (ref "U2") (pin "29") (pinfunction "IO5_29") (pintype "bidirectional"))
    )
    (net (code "26") (name "IO12_3V3IO_0_LOW") (class "Default")
      (node (ref "J4") (pin "2") (pinfunction "2_2") (pintype "passive"))
      (node (ref "R11") (pin "1") (pinfunction "1_1") (pintype "passive"))
      (node (ref "U2") (pin "14") (pinfunction "IO12_14") (pintype "bidirectional"))
    )
    (net (code "27") (name "IO13_ETH_RST") (class "Default")
      (node (ref "R25") (pin "1") (pinfunction "1_1") (pintype "passive"))
      (node (ref "U2") (pin "16") (pinfunction "IO13_16") (pintype "bidirectional"))
    )
    (net (code "28") (name "IO14_LED0B") (class "Default")
      (node (ref "R17") (pin "1") (pinfunction "1_1") (pintype "passive"))
      (node (ref "U2") (pin "13") (pinfunction "IO14_13") (pintype "bidirectional"))
    )
    (net (code "29") (name "IO15_5VIO_2A_UP") (class "Default")
      (node (ref "R10") (pin "2") (pinfunction "2_2") (pintype "passive"))
      (node (ref "U1") (pin "4") (pinfunction "A3_4") (pintype "bidirectional"))
      (node (ref "U2") (pin "23") (pinfunction "IO15_23") (pintype "bidirectional"))
    )
    (net (code "30") (name "IO16_LED1B") (class "Default")
      (node (ref "R23") (pin "1") (pinfunction "1_1") (pintype "passive"))
      (node (ref "U2") (pin "27") (pinfunction "IO16_27") (pintype "bidirectional"))
    )
    (net (code "31") (name "IO32_5VIO_0A") (class "Default")
      (node (ref "U1") (pin "2") (pinfunction "A1_2") (pintype "bidirectional"))
      (node (ref "U2") (pin "8") (pinfunction "IO32_8") (pintype "bidirectional"))
    )
    (net (code "32") (name "IO33_LED0G") (class "Default")
      (node (ref "R18") (pin "1") (pinfunction "1_1") (pintype "passive"))
      (node (ref "U2") (pin "9") (pinfunction "IO33_9") (pintype "bidirectional"))
    )
    (net (code "33") (name "IO34_LED0R") (class "Default")
      (node (ref "R19") (pin "1") (pinfunction "1_1") (pintype "passive"))
      (node (ref "U2") (pin "6") (pinfunction "IO34_6") (pintype "bidirectional"))
    )
    (net (code "34") (name "IO35_5VIO_1A") (class "Default")
      (node (ref "U1") (pin "3") (pinfunction "A2_3") (pintype "bidirectional"))
      (node (ref "U2") (pin "7") (pinfunction "IO35_7") (pintype "bidirectional"))
    )
    (net (code "35") (name "IO36_VSENSE") (class "Default")
      (node (ref "C8") (pin "1") (pinfunction "1_1") (pintype "passive"))
      (node (ref "R13") (pin "1") (pinfunction "1_1") (pintype "passive"))
      (node (ref "R14") (pin "2") (pinfunction "2_2") (pintype "passive"))
      (node (ref "U2") (pin "4") (pinfunction "SENSOR_VP_4") (pintype "input"))
    )
    (net (code "36") (name "IO39_3V3IO_1_LOW") (class "Default")
      (node (ref "J4") (pin "3") (pinfunction "3_3") (pintype "passive"))
      (node (ref "R12") (pin "1") (pinfunction "1_1") (pintype "passive"))
      (node (ref "U2") (pin "5") (pinfunction "SENSOR_VN_5") (pintype "input"))
    )
    (net (code "37") (name "Net-(C16-Pad1)") (class "Default")
      (node (ref "C16") (pin "1") (pinfunction "1_1") (pintype "passive"))
      (node (ref "C32") (pin "1") (pinfunction "1_1") (pintype "passive"))
      (node (ref "J7") (pin "2") (pinfunction "2_2") (pintype "passive"))
      (node (ref "L1") (pin "2") (pinfunction "2_2") (pintype "passive"))
      (node (ref "R20") (pin "2") (pinfunction "2_2") (pintype "passive"))
      (node (ref "R44") (pin "1") (pinfunction "1_1") (pintype "passive"))
    )
    (net (code "38") (name "Net-(D3-B)") (class "Default")
      (node (ref "D3") (pin "4") (pinfunction "B_4") (pintype "passive"))
      (node (ref "R17") (pin "2") (pinfunction "2_2") (pintype "passive"))
    )
    (net (code "39") (name "Net-(D3-G)") (class "Default")
      (node (ref "D3") (pin "3") (pinfunction "G_3") (pintype "passive"))
      (node (ref "R18") (pin "2") (pinfunction "2_2") (pintype "passive"))
    )
    (net (code "40") (name "Net-(D3-R)") (class "Default")
      (node (ref "D3") (pin "1") (pinfunction "R_1") (pintype "passive"))
      (node (ref "R19") (pin "2") (pinfunction "2_2") (pintype "passive"))
    )
    (net (code "41") (name "Net-(D4-PadC)") (class "Default")
      (node (ref "D4") (pin "C") (pinfunction "C_C") (pintype "passive"))
      (node (ref "R23") (pin "2") (pinfunction "2_2") (pintype "passive"))
    )
    (net (code "42") (name "Net-(D5-PadC)") (class "Default")
      (node (ref "D5") (pin "C") (pinfunction "C_C") (pintype "passive"))
      (node (ref "R45") (pin "1") (pinfunction "1_1") (pintype "passive"))
    )
    (net (code "43") (name "Net-(D6-PadC)") (class "Default")
      (node (ref "D6") (pin "C") (pinfunction "C_C") (pintype "passive"))
      (node (ref "R46") (pin "1") (pinfunction "1_1") (pintype "passive"))
    )
    (net (code "44") (name "Net-(D7-PadC)") (class "Default")
      (node (ref "D7") (pin "C") (pinfunction "C_C") (pintype "passive"))
      (node (ref "R24") (pin "2") (pinfunction "2_2") (pintype "passive"))
    )
    (net (code "45") (name "Net-(J5-PadL2)") (class "Default")
      (node (ref "J5") (pin "L2") (pinfunction "L2_L2") (pintype "passive"))
      (node (ref "R40") (pin "2") (pinfunction "2_2") (pintype "passive"))
    )
    (net (code "46") (name "Net-(J5-PadL3)") (class "Default")
      (node (ref "J5") (pin "L3") (pinfunction "L3_L3") (pintype "passive"))
      (node (ref "R41") (pin "2") (pinfunction "2_2") (pintype "passive"))
    )
    (net (code "47") (name "Net-(Q1-B)") (class "Default")
      (node (ref "Q1") (pin "1") (pinfunction "B_1") (pintype "passive"))
      (node (ref "R7") (pin "2") (pinfunction "2_2") (pintype "passive"))
    )
    (net (code "48") (name "Net-(Q2-B)") (class "Default")
      (node (ref "Q2") (pin "1") (pinfunction "B_1") (pintype "passive"))
      (node (ref "R8") (pin "2") (pinfunction "2_2") (pintype "passive"))
    )
    (net (code "49") (name "Net-(U1-OE)") (class "Default")
      (node (ref "R2") (pin "2") (pinfunction "2_2") (pintype "passive"))
      (node (ref "U1") (pin "8") (pinfunction "OE_8") (pintype "input"))
    )
    (net (code "50") (name "Net-(U2-IO17)") (class "Default")
      (node (ref "R5") (pin "1") (pinfunction "1_1") (pintype "passive"))
      (node (ref "U2") (pin "28") (pinfunction "IO17_28") (pintype "bidirectional"))
    )
    (net (code "51") (name "Net-(U3-NOS#)") (class "Default")
      (node (ref "R6") (pin "1") (pinfunction "1_1") (pintype "passive"))
      (node (ref "U3") (pin "20") (pinfunction "NOS#_20") (pintype "power_in"))
    )
    (net (code "52") (name "Net-(U3-RXD)") (class "Default")
      (node (ref "R47") (pin "2") (pinfunction "2_2") (pintype "passive"))
      (node (ref "U3") (pin "4") (pinfunction "RXD_4") (pintype "input"))
    )
    (net (code "53") (name "Net-(U3-TXD)") (class "Default")
      (node (ref "R3") (pin "2") (pinfunction "2_2") (pintype "passive"))
      (node (ref "U3") (pin "3") (pinfunction "TXD_3") (pintype "output"))
    )
    (net (code "54") (name "Net-(U3-XI)") (class "Default")
      (node (ref "C31") (pin "1") (pinfunction "1_1") (pintype "passive"))
      (node (ref "U3") (pin "9") (pinfunction "XI_9") (pintype "input"))
      (node (ref "X2") (pin "3") (pinfunction "2_3") (pintype "bidirectional"))
    )
    (net (code "55") (name "Net-(U3-XO)") (class "Default")
      (node (ref "C30") (pin "1") (pinfunction "1_1") (pintype "passive"))
      (node (ref "U3") (pin "10") (pinfunction "XO_10") (pintype "output"))
      (node (ref "X2") (pin "1") (pinfunction "1_1") (pintype "bidirectional"))
    )
    (net (code "56") (name "Net-(U5-BST)") (class "Default")
      (node (ref "C15") (pin "1") (pinfunction "1_1") (pintype "passive"))
      (node (ref "U5") (pin "1") (pinfunction "BST_1") (pintype "bidirectional"))
    )
    (net (code "57") (name "Net-(U5-EN)") (class "Default")
      (node (ref "R15") (pin "2") (pinfunction "2_2") (pintype "passive"))
      (node (ref "U5") (pin "4") (pinfunction "EN_4") (pintype "bidirectional"))
    )
    (net (code "58") (name "Net-(U5-FB)") (class "Default")
      (node (ref "R20") (pin "1") (pinfunction "1_1") (pintype "passive"))
      (node (ref "R21") (pin "2") (pinfunction "2_2") (pintype "passive"))
      (node (ref "U5") (pin "3") (pinfunction "FB_3") (pintype "bidirectional"))
    )
    (net (code "59") (name "Net-(U5-LX)") (class "Default")
      (node (ref "C15") (pin "2") (pinfunction "2_2") (pintype "passive"))
      (node (ref "D2") (pin "C") (pinfunction "C_C") (pintype "passive"))
      (node (ref "L1") (pin "1") (pinfunction "1_1") (pintype "passive"))
      (node (ref "U5") (pin "6") (pinfunction "LX_6") (pintype "bidirectional"))
    )
    (net (code "60") (name "Net-(U5-VIN)") (class "Default")
      (node (ref "R15") (pin "1") (pinfunction "1_1") (pintype "passive"))
      (node (ref "R43") (pin "2") (pinfunction "2_2") (pintype "passive"))
      (node (ref "U5") (pin "5") (pinfunction "VIN_5") (pintype "bidirectional"))
    )
    (net (code "61") (name "Net-(U6-CRS_DV{slash}MODE2)") (class "Default")
      (node (ref "R31") (pin "1") (pinfunction "1_1") (pintype "passive"))
      (node (ref "R36") (pin "1") (pinfunction "1_1") (pintype "passive"))
      (node (ref "U6") (pin "11") (pinfunction "CRS_DV/MODE2_11") (pintype "bidirectional"))
    )
    (net (code "62") (name "Net-(U6-LED1{slash}REGOFF)") (class "Default")
      (node (ref "R41") (pin "1") (pinfunction "1_1") (pintype "passive"))
      (node (ref "U6") (pin "3") (pinfunction "LED1/REGOFF_3") (pintype "bidirectional"))
    )
    (net (code "63") (name "Net-(U6-LED2{slash}~{NINTSEL})") (class "Default")
      (node (ref "R40") (pin "1") (pinfunction "1_1") (pintype "passive"))
      (node (ref "U6") (pin "2") (pinfunction "LED2/~{NINTSEL}_2") (pintype "bidirectional"))
    )
    (net (code "64") (name "Net-(U6-RBIAS)") (class "Default")
      (node (ref "R28") (pin "2") (pinfunction "2_2") (pintype "passive"))
      (node (ref "U6") (pin "24") (pinfunction "RBIAS_24") (pintype "input"))
    )
    (net (code "65") (name "Net-(U6-RXD0{slash}MODE0)") (class "Default")
      (node (ref "R29") (pin "1") (pinfunction "1_1") (pintype "passive"))
      (node (ref "R34") (pin "1") (pinfunction "1_1") (pintype "passive"))
      (node (ref "U6") (pin "8") (pinfunction "RXD0/MODE0_8") (pintype "bidirectional"))
    )
    (net (code "66") (name "Net-(U6-RXD1{slash}MODE1)") (class "Default")
      (node (ref "R30") (pin "1") (pinfunction "1_1") (pintype "passive"))
      (node (ref "R35") (pin "1") (pinfunction "1_1") (pintype "passive"))
      (node (ref "U6") (pin "7") (pinfunction "RXD1/MODE1_7") (pintype "bidirectional"))
    )
    (net (code "67") (name "Net-(U6-RXER{slash}PHYADO)") (class "Default")
      (node (ref "R32") (pin "2") (pinfunction "2_2") (pintype "passive"))
      (node (ref "U6") (pin "10") (pinfunction "RXER/PHYADO_10") (pintype "bidirectional"))
    )
    (net (code "68") (name "Net-(U6-~{NRST})") (class "Default")
      (node (ref "C20") (pin "1") (pinfunction "1_1") (pintype "passive"))
      (node (ref "R26") (pin "2") (pinfunction "2_2") (pintype "passive"))
      (node (ref "R27") (pin "1") (pinfunction "1_1") (pintype "passive"))
      (node (ref "U6") (pin "15") (pinfunction "~{NRST}_15") (pintype "input"))
    )
    (net (code "69") (name "PHY_VDDCR") (class "Default")
      (node (ref "C22") (pin "1") (pinfunction "1_1") (pintype "passive"))
      (node (ref "C24") (pin "1") (pinfunction "1_1") (pintype "passive"))
      (node (ref "C25") (pin "1") (pinfunction "1_1") (pintype "passive"))
      (node (ref "U6") (pin "6") (pinfunction "VDDCR_6") (pintype "power_in"))
    )
    (net (code "70") (name "RD_N") (class "Default")
      (node (ref "J5") (pin "R8") (pinfunction "RD-_R8") (pintype "input"))
      (node (ref "R37") (pin "1") (pinfunction "1_1") (pintype "passive"))
      (node (ref "U6") (pin "22") (pinfunction "RXN_22") (pintype "bidirectional"))
    )
    (net (code "71") (name "RD_P") (class "Default")
      (node (ref "J5") (pin "R7") (pinfunction "RD+_R7") (pintype "input"))
      (node (ref "R38") (pin "1") (pinfunction "1_1") (pintype "passive"))
      (node (ref "U6") (pin "23") (pinfunction "RXP_23") (pintype "bidirectional"))
    )
    (net (code "72") (name "TD_N") (class "Default")
      (node (ref "J5") (pin "R2") (pinfunction "TD-_R2") (pintype "input"))
      (node (ref "R39") (pin "1") (pinfunction "1_1") (pintype "passive"))
      (node (ref "U6") (pin "20") (pinfunction "TXN_20") (pintype "bidirectional"))
    )
    (net (code "73") (name "TD_P") (class "Default")
      (node (ref "J5") (pin "R1") (pinfunction "TD+_R1") (pintype "input"))
      (node (ref "R42") (pin "1") (pinfunction "1_1") (pintype "passive"))
      (node (ref "U6") (pin "21") (pinfunction "TXP_21") (pintype "bidirectional"))
    )
    (net (code "74") (name "UART_DTR") (class "Default")
      (node (ref "Q1") (pin "2") (pinfunction "E_2") (pintype "passive"))
      (node (ref "R8") (pin "1") (pinfunction "1_1") (pintype "passive"))
      (node (ref "U3") (pin "15") (pinfunction "DTR#_15") (pintype "output"))
    )
    (net (code "75") (name "UART_RTS") (class "Default")
      (node (ref "Q2") (pin "2") (pinfunction "E_2") (pintype "passive"))
      (node (ref "R7") (pin "1") (pinfunction "1_1") (pintype "passive"))
      (node (ref "U3") (pin "16") (pinfunction "RTS#_16") (pintype "output"))
    )
    (net (code "76") (name "UART_RXD") (class "Default")
      (node (ref "R47") (pin "1") (pinfunction "1_1") (pintype "passive"))
      (node (ref "U2") (pin "34") (pinfunction "RXD0_34") (pintype "bidirectional"))
    )
    (net (code "77") (name "UART_TXD") (class "Default")
      (node (ref "R3") (pin "1") (pinfunction "1_1") (pintype "passive"))
      (node (ref "U2") (pin "35") (pinfunction "TXD0_35") (pintype "bidirectional"))
    )
    (net (code "78") (name "USBD_N") (class "Default")
      (node (ref "J1") (pin "2") (pinfunction "2_2") (pintype "passive"))
      (node (ref "U3") (pin "7") (pinfunction "UD-_7") (pintype "bidirectional"))
    )
    (net (code "79") (name "USBD_P") (class "Default")
      (node (ref "J1") (pin "3") (pinfunction "3_3") (pintype "passive"))
      (node (ref "U3") (pin "6") (pinfunction "UD+_6") (pintype "bidirectional"))
    )
    (net (code "80") (name "VBUS") (class "Default")
      (node (ref "C3") (pin "1") (pinfunction "1_1") (pintype "passive"))
      (node (ref "D1") (pin "1") (pinfunction "A_1") (pintype "passive"))
      (node (ref "J1") (pin "1") (pinfunction "1_1") (pintype "passive"))
      (node (ref "R4") (pin "1") (pinfunction "1_1") (pintype "passive"))
    )
    (net (code "81") (name "VDDA") (class "Default")
      (node (ref "C26") (pin "1") (pinfunction "1_1") (pintype "passive"))
      (node (ref "C27") (pin "1") (pinfunction "1_1") (pintype "passive"))
      (node (ref "C28") (pin "1") (pinfunction "1_1") (pintype "passive"))
      (node (ref "C29") (pin "1") (pinfunction "1_1") (pintype "passive"))
      (node (ref "J5") (pin "L1") (pinfunction "L1_L1") (pintype "passive"))
      (node (ref "J5") (pin "R3") (pinfunction "CT_R3") (pintype "input"))
      (node (ref "L2") (pin "2") (pinfunction "2_2") (pintype "passive"))
      (node (ref "R37") (pin "2") (pinfunction "2_2") (pintype "passive"))
      (node (ref "R38") (pin "2") (pinfunction "2_2") (pintype "passive"))
      (node (ref "R39") (pin "2") (pinfunction "2_2") (pintype "passive"))
      (node (ref "R42") (pin "2") (pinfunction "2_2") (pintype "passive"))
      (node (ref "U6") (pin "1") (pinfunction "VDD2A_1") (pintype "power_in"))
      (node (ref "U6") (pin "19") (pinfunction "VDD1A_19") (pintype "power_in"))
    )
    (net (code "82") (name "VLED") (class "Default")
      (node (ref "C11") (pin "1") (pinfunction "1_1") (pintype "passive"))
      (node (ref "C12") (pin "1") (pinfunction "1_1") (pintype "passive"))
      (node (ref "C18") (pin "1") (pinfunction "1_1") (pintype "passive"))
      (node (ref "C19") (pin "1") (pinfunction "1_1") (pintype "passive"))
      (node (ref "J2") (pin "3") (pinfunction "1_3") (pintype "passive"))
      (node (ref "J3") (pin "3") (pinfunction "1_3") (pintype "passive"))
      (node (ref "R13") (pin "2") (pinfunction "2_2") (pintype "passive"))
      (node (ref "R4") (pin "2") (pinfunction "2_2") (pintype "passive"))
      (node (ref "R43") (pin "1") (pinfunction "1_1") (pintype "passive"))
      (node (ref "U4") (pin "3") (pinfunction "VIN_3") (pintype "bidirectional"))
    )
    (net (code "83") (name "unconnected-(J1-Pad4)") (class "Default")
      (node (ref "J1") (pin "4") (pinfunction "4_4") (pintype "passive"))
    )
    (net (code "84") (name "unconnected-(J5-PadR4)") (class "Default")
      (node (ref "J5") (pin "R4") (pinfunction "R4_R4") (pintype "input"))
    )
    (net (code "85") (name "unconnected-(J5-PadR5)") (class "Default")
      (node (ref "J5") (pin "R5") (pinfunction "R5_R5") (pintype "input"))
    )
    (net (code "86") (name "unconnected-(J5-PadR6)") (class "Default")
      (node (ref "J5") (pin "R6") (pinfunction "R6_R6") (pintype "input"))
    )
    (net (code "87") (name "unconnected-(U1-NC-Pad6)") (class "Default")
      (node (ref "U1") (pin "6") (pinfunction "NC_6") (pintype "no_connect"))
    )
    (net (code "88") (name "unconnected-(U1-NC_2-Pad9)") (class "Default")
      (node (ref "U1") (pin "9") (pinfunction "NC_2_9") (pintype "no_connect"))
    )
    (net (code "89") (name "unconnected-(U2-SCL{slash}CLK-Pad20)") (class "Default")
      (node (ref "U2") (pin "20") (pinfunction "SCL/CLK_20") (pintype "bidirectional"))
    )
    (net (code "90") (name "unconnected-(U2-SCS{slash}CMD-Pad19)") (class "Default")
      (node (ref "U2") (pin "19") (pinfunction "SCS/CMD_19") (pintype "bidirectional"))
    )
    (net (code "91") (name "unconnected-(U2-SDI{slash}SD1-Pad22)") (class "Default")
      (node (ref "U2") (pin "22") (pinfunction "SDI/SD1_22") (pintype "bidirectional"))
    )
    (net (code "92") (name "unconnected-(U2-SDO{slash}SD0-Pad21)") (class "Default")
      (node (ref "U2") (pin "21") (pinfunction "SDO/SD0_21") (pintype "bidirectional"))
    )
    (net (code "93") (name "unconnected-(U2-SHD{slash}SD2-Pad17)") (class "Default")
      (node (ref "U2") (pin "17") (pinfunction "SHD/SD2_17") (pintype "bidirectional"))
    )
    (net (code "94") (name "unconnected-(U2-SWP{slash}SD3-Pad18)") (class "Default")
      (node (ref "U2") (pin "18") (pinfunction "SWP/SD3_18") (pintype "bidirectional"))
    )
    (net (code "95") (name "unconnected-(U3-ACT#-Pad2)") (class "Default")
      (node (ref "U3") (pin "2") (pinfunction "ACT#_2") (pintype "output"))
    )
    (net (code "96") (name "unconnected-(U3-CKO-Pad1)") (class "Default")
      (node (ref "U3") (pin "1") (pinfunction "CKO_1") (pintype "output"))
    )
    (net (code "97") (name "unconnected-(U3-CTS#-Pad11)") (class "Default")
      (node (ref "U3") (pin "11") (pinfunction "CTS#_11") (pintype "input"))
    )
    (net (code "98") (name "unconnected-(U3-DCD#-Pad14)") (class "Default")
      (node (ref "U3") (pin "14") (pinfunction "DCD#_14") (pintype "input"))
    )
    (net (code "99") (name "unconnected-(U3-DSR#-Pad12)") (class "Default")
      (node (ref "U3") (pin "12") (pinfunction "DSR#_12") (pintype "input"))
    )
    (net (code "100") (name "unconnected-(U3-NC-Pad17)") (class "Default")
      (node (ref "U3") (pin "17") (pinfunction "NC_17") (pintype "no_connect"))
    )
    (net (code "101") (name "unconnected-(U3-R232-Pad18)") (class "Default")
      (node (ref "U3") (pin "18") (pinfunction "R232_18") (pintype "input"))
    )
    (net (code "102") (name "unconnected-(U3-RI#-Pad13)") (class "Default")
      (node (ref "U3") (pin "13") (pinfunction "RI#_13") (pintype "input"))
    )
    (net (code "103") (name "unconnected-(U6-XTAL2-Pad4)") (class "Default")
      (node (ref "U6") (pin "4") (pinfunction "XTAL2_4") (pintype "output"))
    )
    (net (code "104") (name "unconnected-(U6-~{NINT}{slash}REFCLKO-Pad14)") (class "Default")
      (node (ref "U6") (pin "14") (pinfunction "~{NINT}/REFCLKO_14") (pintype "output"))
    )
    (net (code "105") (name "~{RESET}") (class "Default")
      (node (ref "C2") (pin "1") (pinfunction "1_1") (pintype "passive"))
      (node (ref "Q2") (pin "3") (pinfunction "C_3") (pintype "passive"))
      (node (ref "R1") (pin "1") (pinfunction "1_1") (pintype "passive"))
      (node (ref "S3") (pin "1") (pinfunction "P_1") (pintype "passive"))
      (node (ref "S3") (pin "2") (pinfunction "P1_2") (pintype "passive"))
      (node (ref "U2") (pin "3") (pinfunction "EN_3") (pintype "input"))
    )
  )
)
